# rosscomp_smd.net
KiCad netlist of a schematic drawn in EAGLE
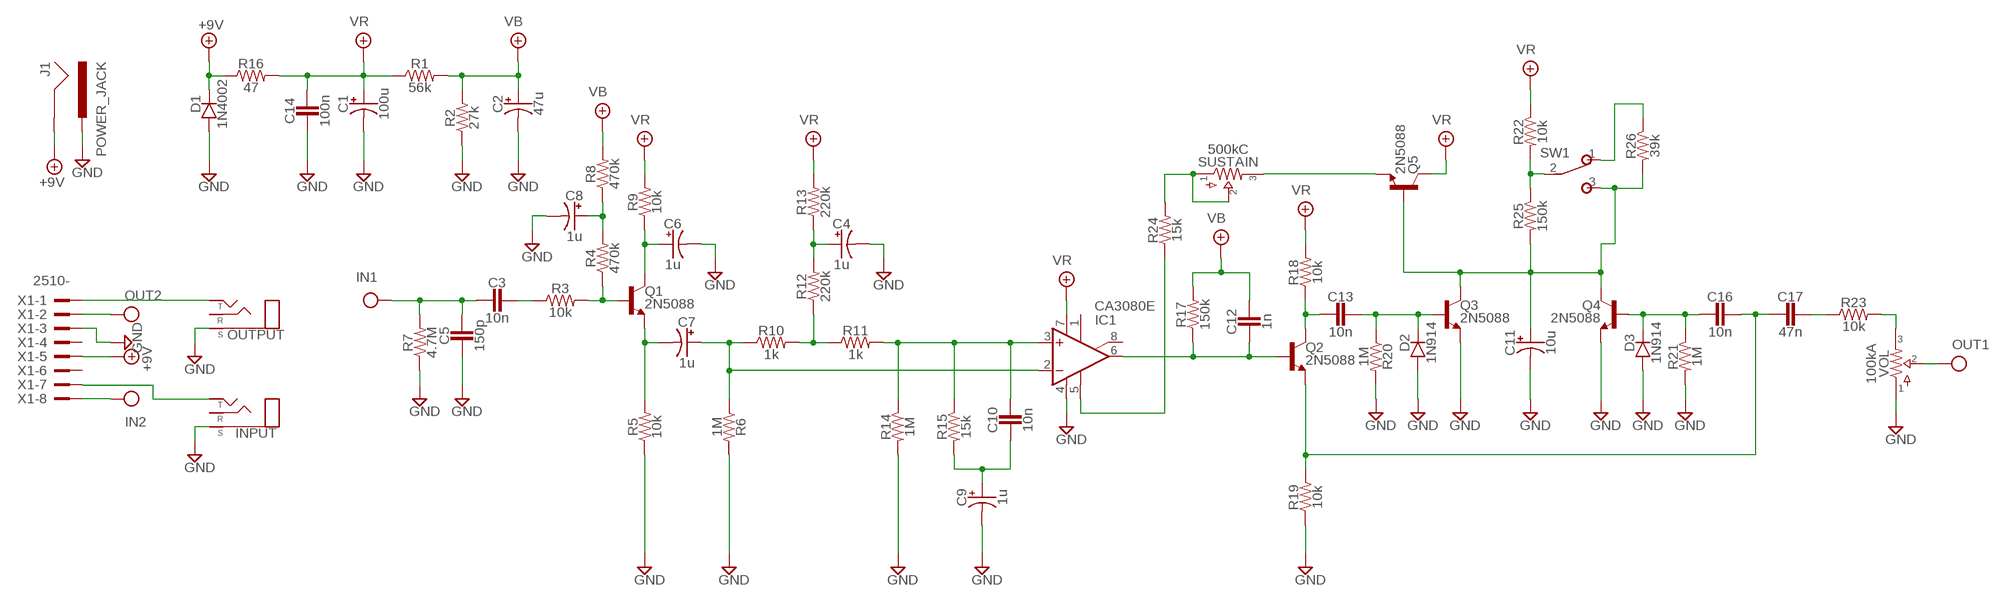
[diagram p0: schematic, sheet 1]

(export (version "E")
  (design (tool "Eeschema 10.0.6"))
  (components
    (comp (ref "C1")
      (value "100u")
      (footprint "eagle-import:CPOL-0605")
      (libsource (lib "eagle-import") (part "CAP-POL0605"))
    )
    (comp (ref "C2")
      (value "47u")
      (footprint "eagle-import:CPOL-0505")
      (libsource (lib "eagle-import") (part "CAP-POL0505"))
    )
    (comp (ref "C3")
      (value "10n")
      (footprint "eagle-import:0805")
      (libsource (lib "eagle-import") (part "CAP0805"))
    )
    (comp (ref "C4")
      (value "1u")
      (footprint "eagle-import:CPOL-0405")
      (libsource (lib "eagle-import") (part "CAP-POL0405"))
    )
    (comp (ref "C5")
      (value "150p")
      (footprint "eagle-import:0805")
      (libsource (lib "eagle-import") (part "CAP0805"))
    )
    (comp (ref "C6")
      (value "1u")
      (footprint "eagle-import:CPOL-0405")
      (libsource (lib "eagle-import") (part "CAP-POL0405"))
    )
    (comp (ref "C7")
      (value "1u")
      (footprint "eagle-import:CPOL-0405")
      (libsource (lib "eagle-import") (part "CAP-POL0405"))
    )
    (comp (ref "C8")
      (value "1u")
      (footprint "eagle-import:CPOL-0405")
      (libsource (lib "eagle-import") (part "CAP-POL0405"))
    )
    (comp (ref "C9")
      (value "1u")
      (footprint "eagle-import:CPOL-0405")
      (libsource (lib "eagle-import") (part "CAP-POL0405"))
    )
    (comp (ref "C10")
      (value "10n")
      (footprint "eagle-import:0805")
      (libsource (lib "eagle-import") (part "CAP0805"))
    )
    (comp (ref "C11")
      (value "10u")
      (footprint "eagle-import:CPOL-0405")
      (libsource (lib "eagle-import") (part "CAP-POL0405"))
    )
    (comp (ref "C12")
      (value "1n")
      (footprint "eagle-import:0805")
      (libsource (lib "eagle-import") (part "CAP0805"))
    )
    (comp (ref "C13")
      (value "10n")
      (footprint "eagle-import:0805")
      (libsource (lib "eagle-import") (part "CAP0805"))
    )
    (comp (ref "C14")
      (value "100n")
      (footprint "eagle-import:0805")
      (libsource (lib "eagle-import") (part "CAP0805"))
    )
    (comp (ref "C16")
      (value "10n")
      (footprint "eagle-import:0805")
      (libsource (lib "eagle-import") (part "CAP0805"))
    )
    (comp (ref "C17")
      (value "47n")
      (footprint "eagle-import:0805")
      (libsource (lib "eagle-import") (part "CAP0805"))
    )
    (comp (ref "D1")
      (value "1N4002")
      (footprint "eagle-import:D-DO214AC")
      (libsource (lib "eagle-import") (part "DIODEDO214AC"))
    )
    (comp (ref "D2")
      (value "1N914")
      (footprint "eagle-import:D-SOD323")
      (libsource (lib "eagle-import") (part "DIODESOD323"))
    )
    (comp (ref "D3")
      (value "1N914")
      (footprint "eagle-import:D-SOD323")
      (libsource (lib "eagle-import") (part "DIODESOD323"))
    )
    (comp (ref "IC1")
      (value "CA3080E")
      (footprint "eagle-import:SO08")
      (libsource (lib "eagle-import") (part "3080SMD"))
    )
    (comp (ref "INPUT")
      (value "STEREONMJ")
      (footprint "eagle-import:NMJ6HCD2")
      (libsource (lib "eagle-import") (part "STEREONMJ"))
    )
    (comp (ref "J1")
      (value "POWER_JACK")
      (footprint "eagle-import:POWER_JACK_PTH")
      (libsource (lib "eagle-import") (part "POWER_JACK"))
    )
    (comp (ref "OUTPUT")
      (value "STEREONMJ")
      (footprint "eagle-import:NMJ6HCD2")
      (libsource (lib "eagle-import") (part "STEREONMJ"))
    )
    (comp (ref "Q1")
      (value "2N5088")
      (footprint "eagle-import:SOT23")
      (libsource (lib "eagle-import") (part "NPNNPN"))
    )
    (comp (ref "Q2")
      (value "2N5088")
      (footprint "eagle-import:SOT23")
      (libsource (lib "eagle-import") (part "NPNNPN"))
    )
    (comp (ref "Q3")
      (value "2N5088")
      (footprint "eagle-import:SOT23")
      (libsource (lib "eagle-import") (part "NPNNPN"))
    )
    (comp (ref "Q4")
      (value "2N5088")
      (footprint "eagle-import:SOT23")
      (libsource (lib "eagle-import") (part "NPNNPN"))
    )
    (comp (ref "Q5")
      (value "2N5088")
      (footprint "eagle-import:SOT23")
      (libsource (lib "eagle-import") (part "NPNNPN"))
    )
    (comp (ref "R1")
      (value "56k")
      (footprint "eagle-import:0805")
      (libsource (lib "eagle-import") (part "RESISTOR0805"))
    )
    (comp (ref "R2")
      (value "27k")
      (footprint "eagle-import:0805")
      (libsource (lib "eagle-import") (part "RESISTOR0805"))
    )
    (comp (ref "R3")
      (value "10k")
      (footprint "eagle-import:0805")
      (libsource (lib "eagle-import") (part "RESISTOR0805"))
    )
    (comp (ref "R4")
      (value "470k")
      (footprint "eagle-import:0805")
      (libsource (lib "eagle-import") (part "RESISTOR0805"))
    )
    (comp (ref "R5")
      (value "10k")
      (footprint "eagle-import:0805")
      (libsource (lib "eagle-import") (part "RESISTOR0805"))
    )
    (comp (ref "R6")
      (value "1M")
      (footprint "eagle-import:0805")
      (libsource (lib "eagle-import") (part "RESISTOR0805"))
    )
    (comp (ref "R7")
      (value "4.7M")
      (footprint "eagle-import:0805")
      (libsource (lib "eagle-import") (part "RESISTOR0805"))
    )
    (comp (ref "R8")
      (value "470k")
      (footprint "eagle-import:0805")
      (libsource (lib "eagle-import") (part "RESISTOR0805"))
    )
    (comp (ref "R9")
      (value "10k")
      (footprint "eagle-import:0805")
      (libsource (lib "eagle-import") (part "RESISTOR0805"))
    )
    (comp (ref "R10")
      (value "1k")
      (footprint "eagle-import:0805")
      (libsource (lib "eagle-import") (part "RESISTOR0805"))
    )
    (comp (ref "R11")
      (value "1k")
      (footprint "eagle-import:0805")
      (libsource (lib "eagle-import") (part "RESISTOR0805"))
    )
    (comp (ref "R12")
      (value "220k")
      (footprint "eagle-import:0805")
      (libsource (lib "eagle-import") (part "RESISTOR0805"))
    )
    (comp (ref "R13")
      (value "220k")
      (footprint "eagle-import:0805")
      (libsource (lib "eagle-import") (part "RESISTOR0805"))
    )
    (comp (ref "R14")
      (value "1M")
      (footprint "eagle-import:0805")
      (libsource (lib "eagle-import") (part "RESISTOR0805"))
    )
    (comp (ref "R15")
      (value "15k")
      (footprint "eagle-import:0805")
      (libsource (lib "eagle-import") (part "RESISTOR0805"))
    )
    (comp (ref "R16")
      (value "47")
      (footprint "eagle-import:1206")
      (libsource (lib "eagle-import") (part "RESISTOR1206"))
    )
    (comp (ref "R17")
      (value "150k")
      (footprint "eagle-import:0805")
      (libsource (lib "eagle-import") (part "RESISTOR0805"))
    )
    (comp (ref "R18")
      (value "10k")
      (footprint "eagle-import:0805")
      (libsource (lib "eagle-import") (part "RESISTOR0805"))
    )
    (comp (ref "R19")
      (value "10k")
      (footprint "eagle-import:0805")
      (libsource (lib "eagle-import") (part "RESISTOR0805"))
    )
    (comp (ref "R20")
      (value "1M")
      (footprint "eagle-import:0805")
      (libsource (lib "eagle-import") (part "RESISTOR0805"))
    )
    (comp (ref "R21")
      (value "1M")
      (footprint "eagle-import:0805")
      (libsource (lib "eagle-import") (part "RESISTOR0805"))
    )
    (comp (ref "R22")
      (value "10k")
      (footprint "eagle-import:0805")
      (libsource (lib "eagle-import") (part "RESISTOR0805"))
    )
    (comp (ref "R23")
      (value "10k")
      (footprint "eagle-import:0805")
      (libsource (lib "eagle-import") (part "RESISTOR0805"))
    )
    (comp (ref "R24")
      (value "15k")
      (footprint "eagle-import:0805")
      (libsource (lib "eagle-import") (part "RESISTOR0805"))
    )
    (comp (ref "R25")
      (value "150k")
      (footprint "eagle-import:0805")
      (libsource (lib "eagle-import") (part "RESISTOR0805"))
    )
    (comp (ref "R26")
      (value "39k")
      (footprint "eagle-import:0805")
      (libsource (lib "eagle-import") (part "RESISTOR0805"))
    )
    (comp (ref "SUSTAIN")
      (value "500kC")
      (footprint "eagle-import:16MM")
      (libsource (lib "eagle-import") (part "POTS16MM"))
    )
    (comp (ref "SW1")
      (value "SPDT")
      (footprint "eagle-import:M9040P")
      (libsource (lib "eagle-import") (part "SPDT"))
    )
    (comp (ref "VOL")
      (value "100kA")
      (footprint "eagle-import:16MM")
      (libsource (lib "eagle-import") (part "POTS16MM"))
    )
    (comp (ref "X1")
      (value "2510-")
      (footprint "eagle-import:PAK100_2500-10")
      (fields (field (name "MF") "3M") (field (name "MPN") "2510-6002UB"))
      (libsource (lib "eagle-import") (part "2510-"))
    )
  )
  (nets
    (net (code "1") (name "+9V") (class "Default")
      (node (ref "D1") (pin "C") (pinfunction "C_C") (pintype "passive"))
      (node (ref "J1") (pin "GND") (pinfunction "GND_GND") (pintype "bidirectional"))
      (node (ref "R16") (pin "1") (pinfunction "1_1") (pintype "passive"))
      (node (ref "X1") (pin "5") (pinfunction "KL_5") (pintype "passive"))
    )
    (net (code "2") (name "GND") (class "Default")
      (node (ref "C1") (pin "-") (pinfunction "-_-") (pintype "passive"))
      (node (ref "C11") (pin "-") (pinfunction "-_-") (pintype "passive"))
      (node (ref "C14") (pin "1") (pinfunction "1_1") (pintype "passive"))
      (node (ref "C2") (pin "-") (pinfunction "-_-") (pintype "passive"))
      (node (ref "C4") (pin "-") (pinfunction "-_-") (pintype "passive"))
      (node (ref "C5") (pin "2") (pinfunction "2_2") (pintype "passive"))
      (node (ref "C6") (pin "-") (pinfunction "-_-") (pintype "passive"))
      (node (ref "C8") (pin "-") (pinfunction "-_-") (pintype "passive"))
      (node (ref "C9") (pin "-") (pinfunction "-_-") (pintype "passive"))
      (node (ref "D1") (pin "A") (pinfunction "A_A") (pintype "passive"))
      (node (ref "D2") (pin "2") (pinfunction "A_2") (pintype "passive"))
      (node (ref "D3") (pin "2") (pinfunction "A_2") (pintype "passive"))
      (node (ref "IC1") (pin "4") (pinfunction "V-_4") (pintype "power_in"))
      (node (ref "INPUT") (pin "S") (pinfunction "S_S") (pintype "passive"))
      (node (ref "J1") (pin "PWR") (pinfunction "PWR_PWR") (pintype "bidirectional"))
      (node (ref "OUTPUT") (pin "S") (pinfunction "S_S") (pintype "passive"))
      (node (ref "Q3") (pin "E") (pinfunction "E_E") (pintype "passive"))
      (node (ref "Q4") (pin "E") (pinfunction "E_E") (pintype "passive"))
      (node (ref "R14") (pin "2") (pinfunction "2_2") (pintype "passive"))
      (node (ref "R19") (pin "1") (pinfunction "1_1") (pintype "passive"))
      (node (ref "R2") (pin "1") (pinfunction "1_1") (pintype "passive"))
      (node (ref "R20") (pin "2") (pinfunction "2_2") (pintype "passive"))
      (node (ref "R21") (pin "2") (pinfunction "2_2") (pintype "passive"))
      (node (ref "R5") (pin "1") (pinfunction "1_1") (pintype "passive"))
      (node (ref "R6") (pin "2") (pinfunction "2_2") (pintype "passive"))
      (node (ref "R7") (pin "1") (pinfunction "1_1") (pintype "passive"))
      (node (ref "VOL") (pin "1") (pinfunction "1_1") (pintype "passive"))
      (node (ref "X1") (pin "3") (pinfunction "KL_3") (pintype "passive"))
    )
    (net (code "3") (name "IN") (class "Default")
      (node (ref "C3") (pin "2") (pinfunction "2_2") (pintype "passive"))
      (node (ref "C5") (pin "1") (pinfunction "1_1") (pintype "passive"))
      (node (ref "R7") (pin "2") (pinfunction "2_2") (pintype "passive"))
      (node (ref "X1") (pin "8") (pinfunction "KL_8") (pintype "passive"))
    )
    (net (code "4") (name "Net-(C3-Pad1)") (class "Default")
      (node (ref "C3") (pin "1") (pinfunction "1_1") (pintype "passive"))
      (node (ref "R3") (pin "1") (pinfunction "1_1") (pintype "passive"))
    )
    (net (code "5") (name "Net-(C4-Pad+)") (class "Default")
      (node (ref "C4") (pin "+") (pinfunction "+_+") (pintype "passive"))
      (node (ref "R12") (pin "2") (pinfunction "2_2") (pintype "passive"))
      (node (ref "R13") (pin "1") (pinfunction "1_1") (pintype "passive"))
    )
    (net (code "6") (name "Net-(C6-Pad+)") (class "Default")
      (node (ref "C6") (pin "+") (pinfunction "+_+") (pintype "passive"))
      (node (ref "Q1") (pin "C") (pinfunction "C_C") (pintype "passive"))
      (node (ref "R9") (pin "1") (pinfunction "1_1") (pintype "passive"))
    )
    (net (code "7") (name "Net-(C7-Pad-)") (class "Default")
      (node (ref "C7") (pin "-") (pinfunction "-_-") (pintype "passive"))
      (node (ref "Q1") (pin "E") (pinfunction "E_E") (pintype "passive"))
      (node (ref "R5") (pin "2") (pinfunction "2_2") (pintype "passive"))
    )
    (net (code "8") (name "Net-(C8-Pad+)") (class "Default")
      (node (ref "C8") (pin "+") (pinfunction "+_+") (pintype "passive"))
      (node (ref "R4") (pin "2") (pinfunction "2_2") (pintype "passive"))
      (node (ref "R8") (pin "1") (pinfunction "1_1") (pintype "passive"))
    )
    (net (code "9") (name "Net-(C10-Pad2)") (class "Default")
      (node (ref "C10") (pin "2") (pinfunction "2_2") (pintype "passive"))
      (node (ref "C9") (pin "+") (pinfunction "+_+") (pintype "passive"))
      (node (ref "R15") (pin "2") (pinfunction "2_2") (pintype "passive"))
    )
    (net (code "10") (name "Net-(C13-Pad2)") (class "Default")
      (node (ref "C13") (pin "2") (pinfunction "2_2") (pintype "passive"))
      (node (ref "Q2") (pin "C") (pinfunction "C_C") (pintype "passive"))
      (node (ref "R18") (pin "1") (pinfunction "1_1") (pintype "passive"))
    )
    (net (code "11") (name "Net-(C16-Pad1)") (class "Default")
      (node (ref "C16") (pin "1") (pinfunction "1_1") (pintype "passive"))
      (node (ref "C17") (pin "2") (pinfunction "2_2") (pintype "passive"))
      (node (ref "Q2") (pin "E") (pinfunction "E_E") (pintype "passive"))
      (node (ref "R19") (pin "2") (pinfunction "2_2") (pintype "passive"))
    )
    (net (code "12") (name "Net-(C17-Pad1)") (class "Default")
      (node (ref "C17") (pin "1") (pinfunction "1_1") (pintype "passive"))
      (node (ref "R23") (pin "1") (pinfunction "1_1") (pintype "passive"))
    )
    (net (code "13") (name "Net-(D2-C)") (class "Default")
      (node (ref "C13") (pin "1") (pinfunction "1_1") (pintype "passive"))
      (node (ref "D2") (pin "1") (pinfunction "C_1") (pintype "passive"))
      (node (ref "Q3") (pin "B") (pinfunction "B_B") (pintype "passive"))
      (node (ref "R20") (pin "1") (pinfunction "1_1") (pintype "passive"))
    )
    (net (code "14") (name "Net-(D3-C)") (class "Default")
      (node (ref "C16") (pin "2") (pinfunction "2_2") (pintype "passive"))
      (node (ref "D3") (pin "1") (pinfunction "C_1") (pintype "passive"))
      (node (ref "Q4") (pin "B") (pinfunction "B_B") (pintype "passive"))
      (node (ref "R21") (pin "1") (pinfunction "1_1") (pintype "passive"))
    )
    (net (code "15") (name "Net-(IC1-+IN)") (class "Default")
      (node (ref "C10") (pin "1") (pinfunction "1_1") (pintype "passive"))
      (node (ref "IC1") (pin "3") (pinfunction "+IN_3") (pintype "input"))
      (node (ref "R11") (pin "2") (pinfunction "2_2") (pintype "passive"))
      (node (ref "R14") (pin "1") (pinfunction "1_1") (pintype "passive"))
      (node (ref "R15") (pin "1") (pinfunction "1_1") (pintype "passive"))
    )
    (net (code "16") (name "Net-(IC1--IN)") (class "Default")
      (node (ref "C7") (pin "+") (pinfunction "+_+") (pintype "passive"))
      (node (ref "IC1") (pin "2") (pinfunction "-IN_2") (pintype "input"))
      (node (ref "R10") (pin "1") (pinfunction "1_1") (pintype "passive"))
      (node (ref "R6") (pin "1") (pinfunction "1_1") (pintype "passive"))
    )
    (net (code "17") (name "Net-(IC1-OPT)") (class "Default")
      (node (ref "IC1") (pin "5") (pinfunction "OPT_5") (pintype "passive"))
      (node (ref "R24") (pin "1") (pinfunction "1_1") (pintype "passive"))
    )
    (net (code "18") (name "Net-(IC1-OUT)") (class "Default")
      (node (ref "C12") (pin "2") (pinfunction "2_2") (pintype "passive"))
      (node (ref "IC1") (pin "6") (pinfunction "OUT_6") (pintype "output"))
      (node (ref "Q2") (pin "B") (pinfunction "B_B") (pintype "passive"))
      (node (ref "R17") (pin "1") (pinfunction "1_1") (pintype "passive"))
    )
    (net (code "19") (name "Net-(Q1-PadB)") (class "Default")
      (node (ref "Q1") (pin "B") (pinfunction "B_B") (pintype "passive"))
      (node (ref "R3") (pin "2") (pinfunction "2_2") (pintype "passive"))
      (node (ref "R4") (pin "1") (pinfunction "1_1") (pintype "passive"))
    )
    (net (code "20") (name "Net-(Q5-PadE)") (class "Default")
      (node (ref "Q5") (pin "E") (pinfunction "E_E") (pintype "passive"))
      (node (ref "SUSTAIN") (pin "3") (pinfunction "3_3") (pintype "passive"))
    )
    (net (code "21") (name "Net-(R10-Pad2)") (class "Default")
      (node (ref "R10") (pin "2") (pinfunction "2_2") (pintype "passive"))
      (node (ref "R11") (pin "1") (pinfunction "1_1") (pintype "passive"))
      (node (ref "R12") (pin "1") (pinfunction "1_1") (pintype "passive"))
    )
    (net (code "22") (name "Net-(R23-Pad2)") (class "Default")
      (node (ref "R23") (pin "2") (pinfunction "2_2") (pintype "passive"))
      (node (ref "VOL") (pin "3") (pinfunction "3_3") (pintype "passive"))
    )
    (net (code "23") (name "Net-(R24-Pad2)") (class "Default")
      (node (ref "R24") (pin "2") (pinfunction "2_2") (pintype "passive"))
      (node (ref "SUSTAIN") (pin "1") (pinfunction "1_1") (pintype "passive"))
      (node (ref "SUSTAIN") (pin "2") (pinfunction "2_2") (pintype "passive"))
    )
    (net (code "24") (name "Net-(SW1-O)") (class "Default")
      (node (ref "R26") (pin "1") (pinfunction "1_1") (pintype "passive"))
      (node (ref "SW1") (pin "1") (pinfunction "O_1") (pintype "passive"))
    )
    (net (code "25") (name "Net-(SW1-P)") (class "Default")
      (node (ref "R22") (pin "2") (pinfunction "2_2") (pintype "passive"))
      (node (ref "R25") (pin "1") (pinfunction "1_1") (pintype "passive"))
      (node (ref "SW1") (pin "2") (pinfunction "P_2") (pintype "passive"))
    )
    (net (code "26") (name "Net-(SW1-S)") (class "Default")
      (node (ref "C11") (pin "+") (pinfunction "+_+") (pintype "passive"))
      (node (ref "Q3") (pin "C") (pinfunction "C_C") (pintype "passive"))
      (node (ref "Q4") (pin "C") (pinfunction "C_C") (pintype "passive"))
      (node (ref "Q5") (pin "B") (pinfunction "B_B") (pintype "passive"))
      (node (ref "R25") (pin "2") (pinfunction "2_2") (pintype "passive"))
      (node (ref "R26") (pin "2") (pinfunction "2_2") (pintype "passive"))
      (node (ref "SW1") (pin "3") (pinfunction "S_3") (pintype "passive"))
    )
    (net (code "27") (name "Net-(X1A-KL)") (class "Default")
      (node (ref "OUTPUT") (pin "T") (pinfunction "T_T") (pintype "passive"))
      (node (ref "X1") (pin "1") (pinfunction "KL_1") (pintype "passive"))
    )
    (net (code "28") (name "Net-(X1G-KL)") (class "Default")
      (node (ref "INPUT") (pin "T") (pinfunction "T_T") (pintype "passive"))
      (node (ref "X1") (pin "7") (pinfunction "KL_7") (pintype "passive"))
    )
    (net (code "29") (name "OUT") (class "Default")
      (node (ref "VOL") (pin "2") (pinfunction "2_2") (pintype "passive"))
      (node (ref "X1") (pin "2") (pinfunction "KL_2") (pintype "passive"))
    )
    (net (code "30") (name "VB") (class "Default")
      (node (ref "C12") (pin "1") (pinfunction "1_1") (pintype "passive"))
      (node (ref "C2") (pin "+") (pinfunction "+_+") (pintype "passive"))
      (node (ref "R1") (pin "2") (pinfunction "2_2") (pintype "passive"))
      (node (ref "R17") (pin "2") (pinfunction "2_2") (pintype "passive"))
      (node (ref "R2") (pin "2") (pinfunction "2_2") (pintype "passive"))
      (node (ref "R8") (pin "2") (pinfunction "2_2") (pintype "passive"))
    )
    (net (code "31") (name "VR") (class "Default")
      (node (ref "C1") (pin "+") (pinfunction "+_+") (pintype "passive"))
      (node (ref "C14") (pin "2") (pinfunction "2_2") (pintype "passive"))
      (node (ref "IC1") (pin "7") (pinfunction "V+_7") (pintype "power_in"))
      (node (ref "Q5") (pin "C") (pinfunction "C_C") (pintype "passive"))
      (node (ref "R1") (pin "1") (pinfunction "1_1") (pintype "passive"))
      (node (ref "R13") (pin "2") (pinfunction "2_2") (pintype "passive"))
      (node (ref "R16") (pin "2") (pinfunction "2_2") (pintype "passive"))
      (node (ref "R18") (pin "2") (pinfunction "2_2") (pintype "passive"))
      (node (ref "R22") (pin "1") (pinfunction "1_1") (pintype "passive"))
      (node (ref "R9") (pin "2") (pinfunction "2_2") (pintype "passive"))
    )
    (net (code "32") (name "unconnected-(IC1-ON1-Pad1)") (class "Default")
      (node (ref "IC1") (pin "1") (pinfunction "ON1_1") (pintype "passive"))
    )
    (net (code "33") (name "unconnected-(IC1-ON2-Pad8)") (class "Default")
      (node (ref "IC1") (pin "8") (pinfunction "ON2_8") (pintype "passive"))
    )
    (net (code "34") (name "unconnected-(INPUT-PadR)") (class "Default")
      (node (ref "INPUT") (pin "R") (pinfunction "R_R") (pintype "passive"))
    )
    (net (code "35") (name "unconnected-(OUTPUT-PadR)") (class "Default")
      (node (ref "OUTPUT") (pin "R") (pinfunction "R_R") (pintype "passive"))
    )
    (net (code "36") (name "unconnected-(X1D-KL-Pad4)") (class "Default")
      (node (ref "X1") (pin "4") (pinfunction "KL_4") (pintype "passive"))
    )
    (net (code "37") (name "unconnected-(X1F-KL-Pad6)") (class "Default")
      (node (ref "X1") (pin "6") (pinfunction "KL_6") (pintype "passive"))
    )
  )
)
